# main.net
KiCad netlist of a schematic drawn in Altium Designer
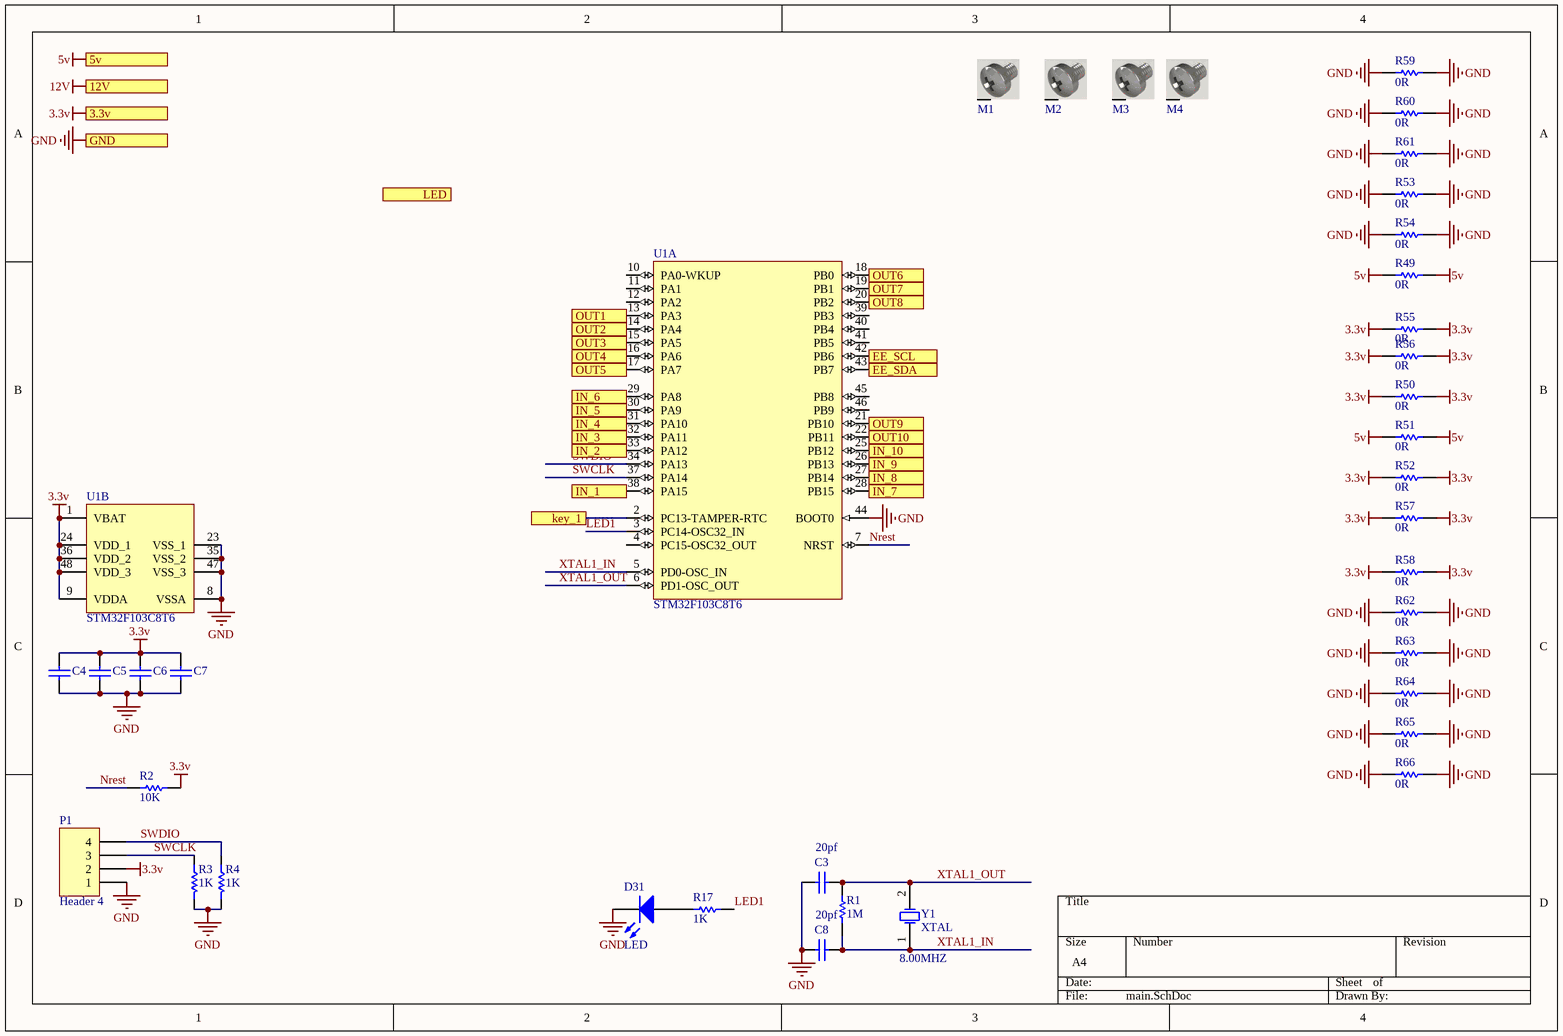
[diagram p0: main.SchDoc]

(export (version "E")
  (design (tool "Eeschema 10.0.6"))
  (components
    (comp (ref "C3")
      (value "20pf")
      (footprint "RES 0805 (2012X06L)")
      (description "Capacitor")
      (fields (field (name "PUBLISHER") "Altium Limited"))
      (libsource (lib "Miscellaneous Devices") (part "Cap"))
    )
    (comp (ref "C4")
      (value "~")
      (footprint "RES 0805 (2012X06L)")
      (description "Capacitor")
      (fields (field (name "PUBLISHER") "Altium Limited"))
      (libsource (lib "Miscellaneous Devices") (part "Cap"))
    )
    (comp (ref "C5")
      (value "~")
      (footprint "RES 0805 (2012X06L)")
      (description "Capacitor")
      (fields (field (name "PUBLISHER") "Altium Limited"))
      (libsource (lib "Miscellaneous Devices") (part "Cap"))
    )
    (comp (ref "C6")
      (value "~")
      (footprint "RES 0805 (2012X06L)")
      (description "Capacitor")
      (fields (field (name "PUBLISHER") "Altium Limited"))
      (libsource (lib "Miscellaneous Devices") (part "Cap"))
    )
    (comp (ref "C7")
      (value "~")
      (footprint "RES 0805 (2012X06L)")
      (description "Capacitor")
      (fields (field (name "PUBLISHER") "Altium Limited"))
      (libsource (lib "Miscellaneous Devices") (part "Cap"))
    )
    (comp (ref "C8")
      (value "20pf")
      (footprint "RES 0805 (2012X06L)")
      (description "Capacitor")
      (fields (field (name "PUBLISHER") "Altium Limited"))
      (libsource (lib "Miscellaneous Devices") (part "Cap"))
    )
    (comp (ref "D31") (value "LED") (footprint "led 5mm") (libsource (lib "m_faryabi") (part "LED")))
    (comp (ref "M1")
      (value "Screw")
      (footprint "Board Screw")
      (description "Board Screw With Spacer")
      (libsource (lib "m_faryabi") (part "Pich"))
    )
    (comp (ref "M2")
      (value "Screw")
      (footprint "Board Screw")
      (description "Board Screw With Spacer")
      (libsource (lib "m_faryabi") (part "Pich"))
    )
    (comp (ref "M3")
      (value "Screw")
      (footprint "Board Screw")
      (description "Board Screw With Spacer")
      (libsource (lib "m_faryabi") (part "Pich"))
    )
    (comp (ref "M4")
      (value "Screw")
      (footprint "Board Screw")
      (description "Board Screw With Spacer")
      (libsource (lib "m_faryabi") (part "Pich"))
    )
    (comp (ref "P1")
      (value "Header 4")
      (footprint "HDR1X4")
      (description "Header, 4-Pin")
      (fields (field (name "PUBLISHER") "Altium Limited"))
      (libsource (lib "Miscellaneous Connectors") (part "Header 4"))
    )
    (comp (ref "R1")
      (value "1M")
      (footprint "RES 0805 (2012X06L)")
      (description "Resistor")
      (fields (field (name "Comment") "Res1") (field (name "PUBLISHER") "Altium Limited"))
      (libsource (lib "Miscellaneous Devices") (part "Res1"))
    )
    (comp (ref "R2")
      (value "~")
      (footprint "RES 0805 (2012X06L)")
      (fields (field (name "VALV") "10K"))
      (libsource (lib "m_faryabi_1") (part "resistor"))
    )
    (comp (ref "R3")
      (value "1K")
      (footprint "RES 0805 (2012X06L)")
      (description "Resistor")
      (fields (field (name "TOLERANCE") "5%") (field (name "POWER") "1/8 W"))
      (libsource (lib "My Library") (part "Resistor"))
    )
    (comp (ref "R4")
      (value "1K")
      (footprint "RES 0805 (2012X06L)")
      (description "Resistor")
      (fields (field (name "TOLERANCE") "5%") (field (name "POWER") "1/8 W"))
      (libsource (lib "My Library") (part "Resistor"))
    )
    (comp (ref "R17")
      (value "1K")
      (footprint "RES 0805 (2012X06L)")
      (fields (field (name "Comment") "resistor"))
      (libsource (lib "m_faryabi") (part "resistor"))
    )
    (comp (ref "R49")
      (value "0R")
      (footprint "RES 0805 optional")
      (fields (field (name "Comment") "resistor"))
      (libsource (lib "m_faryabi") (part "resistor"))
    )
    (comp (ref "R50")
      (value "0R")
      (footprint "RES 0805 optional")
      (fields (field (name "Comment") "resistor"))
      (libsource (lib "m_faryabi") (part "resistor"))
    )
    (comp (ref "R51")
      (value "0R")
      (footprint "RES 0805 optional")
      (fields (field (name "Comment") "resistor"))
      (libsource (lib "m_faryabi") (part "resistor"))
    )
    (comp (ref "R52")
      (value "0R")
      (footprint "RES 0805 optional")
      (fields (field (name "Comment") "resistor"))
      (libsource (lib "m_faryabi") (part "resistor"))
    )
    (comp (ref "R53")
      (value "0R")
      (footprint "RES 0805 optional")
      (fields (field (name "Comment") "resistor"))
      (libsource (lib "m_faryabi") (part "resistor"))
    )
    (comp (ref "R54")
      (value "0R")
      (footprint "RES 0805 optional")
      (fields (field (name "Comment") "resistor"))
      (libsource (lib "m_faryabi") (part "resistor"))
    )
    (comp (ref "R55")
      (value "0R")
      (footprint "RES 0805 optional")
      (fields (field (name "Comment") "resistor"))
      (libsource (lib "m_faryabi") (part "resistor"))
    )
    (comp (ref "R56")
      (value "0R")
      (footprint "RES 0805 optional")
      (fields (field (name "Comment") "resistor"))
      (libsource (lib "m_faryabi") (part "resistor"))
    )
    (comp (ref "R57")
      (value "0R")
      (footprint "RES 0805 optional")
      (fields (field (name "Comment") "resistor"))
      (libsource (lib "m_faryabi") (part "resistor"))
    )
    (comp (ref "R58")
      (value "0R")
      (footprint "RES 0805 optional")
      (fields (field (name "Comment") "resistor"))
      (libsource (lib "m_faryabi") (part "resistor"))
    )
    (comp (ref "R59")
      (value "0R")
      (footprint "RES 0805 optional")
      (fields (field (name "Comment") "resistor"))
      (libsource (lib "m_faryabi") (part "resistor"))
    )
    (comp (ref "R60")
      (value "0R")
      (footprint "RES 0805 optional")
      (fields (field (name "Comment") "resistor"))
      (libsource (lib "m_faryabi") (part "resistor"))
    )
    (comp (ref "R61")
      (value "0R")
      (footprint "RES 0805 optional")
      (fields (field (name "Comment") "resistor"))
      (libsource (lib "m_faryabi") (part "resistor"))
    )
    (comp (ref "R62")
      (value "0R")
      (footprint "RES 0805 optional")
      (fields (field (name "Comment") "resistor"))
      (libsource (lib "m_faryabi") (part "resistor"))
    )
    (comp (ref "R63")
      (value "0R")
      (footprint "RES 0805 optional")
      (fields (field (name "Comment") "resistor"))
      (libsource (lib "m_faryabi") (part "resistor"))
    )
    (comp (ref "R64")
      (value "0R")
      (footprint "RES 0805 optional")
      (fields (field (name "Comment") "resistor"))
      (libsource (lib "m_faryabi") (part "resistor"))
    )
    (comp (ref "R65")
      (value "0R")
      (footprint "RES 0805 optional")
      (fields (field (name "Comment") "resistor"))
      (libsource (lib "m_faryabi") (part "resistor"))
    )
    (comp (ref "R66")
      (value "0R")
      (footprint "RES 0805 optional")
      (fields (field (name "Comment") "resistor"))
      (libsource (lib "m_faryabi") (part "resistor"))
    )
    (comp (ref "U1")
      (value "STM32F103C8T6")
      (footprint "STM-LQFP48_N")
      (libsource (lib "STMicroelectronics STM32 F1") (part "STM32F103C8T6"))
    )
    (comp (ref "Y1")
      (value "XTAL")
      (footprint "Xtal")
      (fields (field (name "ALTIUM_UNNAMED_1") "8.00MHZ"))
      (libsource (lib "m_faryabi_1") (part "XTAL"))
    )
  )
  (nets
    (net (code "1") (name "/EE_SCL") (class "Default")
      (node (ref "U1") (pin "42") (pinfunction "PB6_42") (pintype "bidirectional"))
    )
    (net (code "2") (name "/EE_SDA") (class "Default")
      (node (ref "U1") (pin "43") (pinfunction "PB7_43") (pintype "bidirectional"))
    )
    (net (code "3") (name "/IN_1") (class "Default")
      (node (ref "U1") (pin "38") (pinfunction "PA15_38") (pintype "bidirectional"))
    )
    (net (code "4") (name "/IN_2") (class "Default")
      (node (ref "U1") (pin "33") (pinfunction "PA12_33") (pintype "bidirectional"))
    )
    (net (code "5") (name "/IN_3") (class "Default")
      (node (ref "U1") (pin "32") (pinfunction "PA11_32") (pintype "bidirectional"))
    )
    (net (code "6") (name "/IN_4") (class "Default")
      (node (ref "U1") (pin "31") (pinfunction "PA10_31") (pintype "bidirectional"))
    )
    (net (code "7") (name "/IN_5") (class "Default")
      (node (ref "U1") (pin "30") (pinfunction "PA9_30") (pintype "bidirectional"))
    )
    (net (code "8") (name "/IN_6") (class "Default")
      (node (ref "U1") (pin "29") (pinfunction "PA8_29") (pintype "bidirectional"))
    )
    (net (code "9") (name "/IN_7") (class "Default")
      (node (ref "U1") (pin "28") (pinfunction "PB15_28") (pintype "bidirectional"))
    )
    (net (code "10") (name "/IN_8") (class "Default")
      (node (ref "U1") (pin "27") (pinfunction "PB14_27") (pintype "bidirectional"))
    )
    (net (code "11") (name "/IN_9") (class "Default")
      (node (ref "U1") (pin "26") (pinfunction "PB13_26") (pintype "bidirectional"))
    )
    (net (code "12") (name "/IN_10") (class "Default")
      (node (ref "U1") (pin "25") (pinfunction "PB12_25") (pintype "bidirectional"))
    )
    (net (code "14") (name "/LED1") (class "Default")
      (node (ref "R17") (pin "2") (pinfunction "2_2") (pintype "passive"))
      (node (ref "U1") (pin "3") (pinfunction "PC14-OSC32_IN_3") (pintype "bidirectional"))
    )
    (net (code "15") (name "/Nrest") (class "Default")
      (node (ref "R2") (pin "1") (pinfunction "1_1") (pintype "passive"))
      (node (ref "U1") (pin "7") (pinfunction "NRST_7") (pintype "bidirectional"))
    )
    (net (code "16") (name "/OUT1") (class "Default")
      (node (ref "U1") (pin "13") (pinfunction "PA3_13") (pintype "bidirectional"))
    )
    (net (code "17") (name "/OUT2") (class "Default")
      (node (ref "U1") (pin "14") (pinfunction "PA4_14") (pintype "bidirectional"))
    )
    (net (code "18") (name "/OUT3") (class "Default")
      (node (ref "U1") (pin "15") (pinfunction "PA5_15") (pintype "bidirectional"))
    )
    (net (code "19") (name "/OUT4") (class "Default")
      (node (ref "U1") (pin "16") (pinfunction "PA6_16") (pintype "bidirectional"))
    )
    (net (code "20") (name "/OUT5") (class "Default")
      (node (ref "U1") (pin "17") (pinfunction "PA7_17") (pintype "bidirectional"))
    )
    (net (code "21") (name "/OUT6") (class "Default")
      (node (ref "U1") (pin "18") (pinfunction "PB0_18") (pintype "bidirectional"))
    )
    (net (code "22") (name "/OUT7") (class "Default")
      (node (ref "U1") (pin "19") (pinfunction "PB1_19") (pintype "bidirectional"))
    )
    (net (code "23") (name "/OUT8") (class "Default")
      (node (ref "U1") (pin "20") (pinfunction "PB2_20") (pintype "bidirectional"))
    )
    (net (code "24") (name "/OUT9") (class "Default")
      (node (ref "U1") (pin "21") (pinfunction "PB10_21") (pintype "bidirectional"))
    )
    (net (code "25") (name "/OUT10") (class "Default")
      (node (ref "U1") (pin "22") (pinfunction "PB11_22") (pintype "bidirectional"))
    )
    (net (code "26") (name "/SWCLK") (class "Default")
      (node (ref "P1") (pin "3") (pinfunction "3_3") (pintype "passive"))
      (node (ref "R3") (pin "1") (pinfunction "1_1") (pintype "passive"))
      (node (ref "U1") (pin "37") (pinfunction "PA14_37") (pintype "bidirectional"))
    )
    (net (code "27") (name "/SWDIO") (class "Default")
      (node (ref "P1") (pin "4") (pinfunction "4_4") (pintype "passive"))
      (node (ref "R4") (pin "1") (pinfunction "1_1") (pintype "passive"))
      (node (ref "U1") (pin "34") (pinfunction "PA13_34") (pintype "bidirectional"))
    )
    (net (code "28") (name "/XTAL1_IN") (class "Default")
      (node (ref "C8") (pin "1") (pinfunction "1_1") (pintype "passive"))
      (node (ref "R1") (pin "1") (pinfunction "1_1") (pintype "passive"))
      (node (ref "U1") (pin "5") (pinfunction "PD0-OSC_IN_5") (pintype "bidirectional"))
      (node (ref "Y1") (pin "1") (pinfunction "OSC1_1") (pintype "passive"))
    )
    (net (code "29") (name "/XTAL1_OUT") (class "Default")
      (node (ref "C3") (pin "1") (pinfunction "1_1") (pintype "passive"))
      (node (ref "R1") (pin "2") (pinfunction "2_2") (pintype "passive"))
      (node (ref "U1") (pin "6") (pinfunction "PD1-OSC_OUT_6") (pintype "bidirectional"))
      (node (ref "Y1") (pin "2") (pinfunction "OSC2_2") (pintype "passive"))
    )
    (net (code "30") (name "/key_1") (class "Default")
      (node (ref "U1") (pin "2") (pinfunction "PC13-TAMPER-RTC_2") (pintype "bidirectional"))
    )
    (net (code "31") (name "3.3v") (class "Default")
      (node (ref "C4") (pin "2") (pinfunction "2_2") (pintype "passive"))
      (node (ref "C5") (pin "2") (pinfunction "2_2") (pintype "passive"))
      (node (ref "C6") (pin "2") (pinfunction "2_2") (pintype "passive"))
      (node (ref "C7") (pin "2") (pinfunction "2_2") (pintype "passive"))
      (node (ref "P1") (pin "2") (pinfunction "2_2") (pintype "passive"))
      (node (ref "R2") (pin "2") (pinfunction "2_2") (pintype "passive"))
      (node (ref "R50") (pin "1") (pinfunction "1_1") (pintype "passive"))
      (node (ref "R50") (pin "2") (pinfunction "2_2") (pintype "passive"))
      (node (ref "R52") (pin "1") (pinfunction "1_1") (pintype "passive"))
      (node (ref "R52") (pin "2") (pinfunction "2_2") (pintype "passive"))
      (node (ref "R55") (pin "1") (pinfunction "1_1") (pintype "passive"))
      (node (ref "R55") (pin "2") (pinfunction "2_2") (pintype "passive"))
      (node (ref "R56") (pin "1") (pinfunction "1_1") (pintype "passive"))
      (node (ref "R56") (pin "2") (pinfunction "2_2") (pintype "passive"))
      (node (ref "R57") (pin "1") (pinfunction "1_1") (pintype "passive"))
      (node (ref "R57") (pin "2") (pinfunction "2_2") (pintype "passive"))
      (node (ref "R58") (pin "1") (pinfunction "1_1") (pintype "passive"))
      (node (ref "R58") (pin "2") (pinfunction "2_2") (pintype "passive"))
      (node (ref "U1") (pin "1") (pinfunction "VBAT_1") (pintype "power_in"))
      (node (ref "U1") (pin "24") (pinfunction "VDD_1_24") (pintype "power_in"))
      (node (ref "U1") (pin "36") (pinfunction "VDD_2_36") (pintype "power_in"))
      (node (ref "U1") (pin "48") (pinfunction "VDD_3_48") (pintype "power_in"))
      (node (ref "U1") (pin "9") (pinfunction "VDDA_9") (pintype "power_in"))
    )
    (net (code "32") (name "5v") (class "Default")
      (node (ref "R49") (pin "1") (pinfunction "1_1") (pintype "passive"))
      (node (ref "R49") (pin "2") (pinfunction "2_2") (pintype "passive"))
      (node (ref "R51") (pin "1") (pinfunction "1_1") (pintype "passive"))
      (node (ref "R51") (pin "2") (pinfunction "2_2") (pintype "passive"))
    )
    (net (code "34") (name "GND") (class "Default")
      (node (ref "C3") (pin "2") (pinfunction "2_2") (pintype "passive"))
      (node (ref "C4") (pin "1") (pinfunction "1_1") (pintype "passive"))
      (node (ref "C5") (pin "1") (pinfunction "1_1") (pintype "passive"))
      (node (ref "C6") (pin "1") (pinfunction "1_1") (pintype "passive"))
      (node (ref "C7") (pin "1") (pinfunction "1_1") (pintype "passive"))
      (node (ref "C8") (pin "2") (pinfunction "2_2") (pintype "passive"))
      (node (ref "D31") (pin "2") (pinfunction "K_2") (pintype "passive"))
      (node (ref "P1") (pin "1") (pinfunction "1_1") (pintype "passive"))
      (node (ref "R3") (pin "2") (pinfunction "2_2") (pintype "passive"))
      (node (ref "R4") (pin "2") (pinfunction "2_2") (pintype "passive"))
      (node (ref "R53") (pin "1") (pinfunction "1_1") (pintype "passive"))
      (node (ref "R53") (pin "2") (pinfunction "2_2") (pintype "passive"))
      (node (ref "R54") (pin "1") (pinfunction "1_1") (pintype "passive"))
      (node (ref "R54") (pin "2") (pinfunction "2_2") (pintype "passive"))
      (node (ref "R59") (pin "1") (pinfunction "1_1") (pintype "passive"))
      (node (ref "R59") (pin "2") (pinfunction "2_2") (pintype "passive"))
      (node (ref "R60") (pin "1") (pinfunction "1_1") (pintype "passive"))
      (node (ref "R60") (pin "2") (pinfunction "2_2") (pintype "passive"))
      (node (ref "R61") (pin "1") (pinfunction "1_1") (pintype "passive"))
      (node (ref "R61") (pin "2") (pinfunction "2_2") (pintype "passive"))
      (node (ref "R62") (pin "1") (pinfunction "1_1") (pintype "passive"))
      (node (ref "R62") (pin "2") (pinfunction "2_2") (pintype "passive"))
      (node (ref "R63") (pin "1") (pinfunction "1_1") (pintype "passive"))
      (node (ref "R63") (pin "2") (pinfunction "2_2") (pintype "passive"))
      (node (ref "R64") (pin "1") (pinfunction "1_1") (pintype "passive"))
      (node (ref "R64") (pin "2") (pinfunction "2_2") (pintype "passive"))
      (node (ref "R65") (pin "1") (pinfunction "1_1") (pintype "passive"))
      (node (ref "R65") (pin "2") (pinfunction "2_2") (pintype "passive"))
      (node (ref "R66") (pin "1") (pinfunction "1_1") (pintype "passive"))
      (node (ref "R66") (pin "2") (pinfunction "2_2") (pintype "passive"))
      (node (ref "U1") (pin "23") (pinfunction "VSS_1_23") (pintype "power_in"))
      (node (ref "U1") (pin "35") (pinfunction "VSS_2_35") (pintype "power_in"))
      (node (ref "U1") (pin "44") (pinfunction "BOOT0_44") (pintype "input"))
      (node (ref "U1") (pin "47") (pinfunction "VSS_3_47") (pintype "power_in"))
      (node (ref "U1") (pin "8") (pinfunction "VSSA_8") (pintype "power_in"))
    )
    (net (code "35") (name "Net-(D31-A)") (class "Default")
      (node (ref "D31") (pin "1") (pinfunction "A_1") (pintype "passive"))
      (node (ref "R17") (pin "1") (pinfunction "1_1") (pintype "passive"))
    )
    (net (code "36") (name "unconnected-(M1-PadS)") (class "Default")
      (node (ref "M1") (pin "S") (pinfunction "S_S") (pintype "passive"))
    )
    (net (code "37") (name "unconnected-(M2-PadS)") (class "Default")
      (node (ref "M2") (pin "S") (pinfunction "S_S") (pintype "passive"))
    )
    (net (code "38") (name "unconnected-(M3-PadS)") (class "Default")
      (node (ref "M3") (pin "S") (pinfunction "S_S") (pintype "passive"))
    )
    (net (code "39") (name "unconnected-(M4-PadS)") (class "Default")
      (node (ref "M4") (pin "S") (pinfunction "S_S") (pintype "passive"))
    )
    (net (code "40") (name "unconnected-(U1A-PA0-WKUP-Pad10)") (class "Default")
      (node (ref "U1") (pin "10") (pinfunction "PA0-WKUP_10") (pintype "bidirectional"))
    )
    (net (code "41") (name "unconnected-(U1A-PA1-Pad11)") (class "Default")
      (node (ref "U1") (pin "11") (pinfunction "PA1_11") (pintype "bidirectional"))
    )
    (net (code "42") (name "unconnected-(U1A-PA2-Pad12)") (class "Default")
      (node (ref "U1") (pin "12") (pinfunction "PA2_12") (pintype "bidirectional"))
    )
    (net (code "43") (name "unconnected-(U1A-PB3-Pad39)") (class "Default")
      (node (ref "U1") (pin "39") (pinfunction "PB3_39") (pintype "bidirectional"))
    )
    (net (code "44") (name "unconnected-(U1A-PB4-Pad40)") (class "Default")
      (node (ref "U1") (pin "40") (pinfunction "PB4_40") (pintype "bidirectional"))
    )
    (net (code "45") (name "unconnected-(U1A-PB5-Pad41)") (class "Default")
      (node (ref "U1") (pin "41") (pinfunction "PB5_41") (pintype "bidirectional"))
    )
    (net (code "46") (name "unconnected-(U1A-PB8-Pad45)") (class "Default")
      (node (ref "U1") (pin "45") (pinfunction "PB8_45") (pintype "bidirectional"))
    )
    (net (code "47") (name "unconnected-(U1A-PB9-Pad46)") (class "Default")
      (node (ref "U1") (pin "46") (pinfunction "PB9_46") (pintype "bidirectional"))
    )
    (net (code "48") (name "unconnected-(U1A-PC15-OSC32_OUT-Pad4)") (class "Default")
      (node (ref "U1") (pin "4") (pinfunction "PC15-OSC32_OUT_4") (pintype "bidirectional"))
    )
  )
)
